# LIDO-HW_100_InputStage_2.net
KiCad netlist of a schematic drawn in Altium Designer
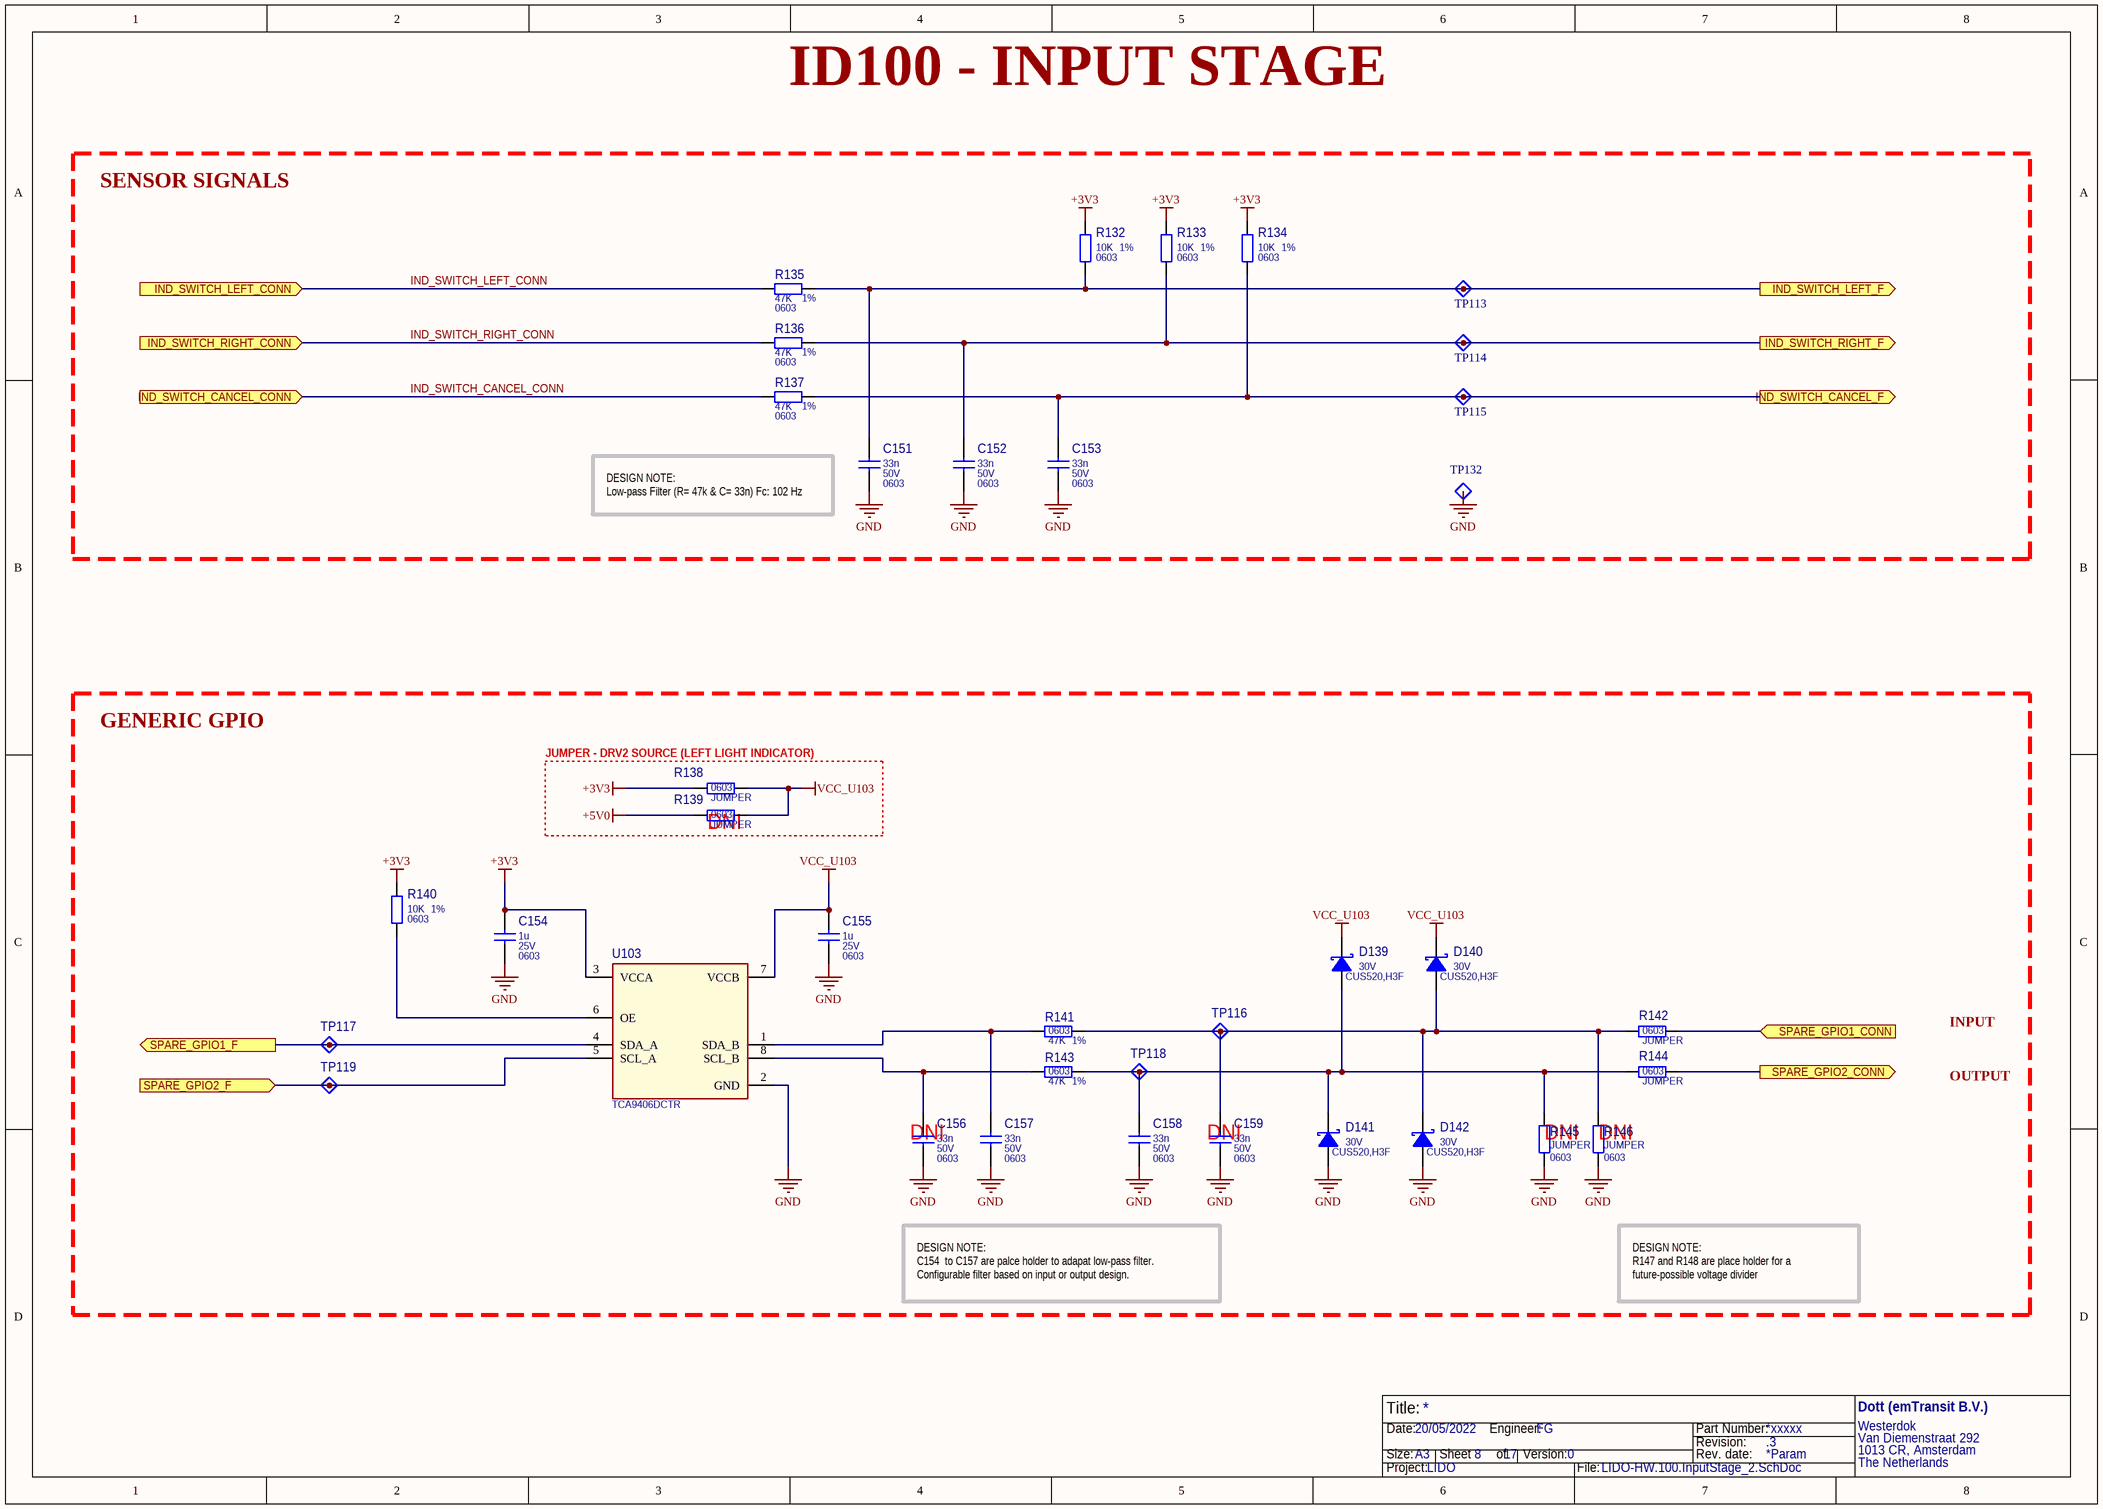
[diagram p0: LIDO-HW.100.InputStage_2.SchDoc]

(export (version "E")
  (design (tool "Eeschema 10.0.6"))
  (components
    (comp (ref "C151")
      (value "33n")
      (footprint "CAP_0603_1608X90-N_MURATA_A")
      (description "CAP CER 0.033UF 50V X7R 0603")
      (fields
        (field (name "MANUFACTURER PART NUMBER") "CGA3E2X7R1H333K080AA")
        (field (name "MANUFACTURER") "TDK Corporation")
        (field (name "PART VALUE 2") "50V")
        (field (name "PART PACKAGE") "0603")
      )
      (libsource (lib "DB_Library") (part "Ceramic"))
    )
    (comp (ref "C152")
      (value "33n")
      (footprint "CAP_0603_1608X90-N_MURATA_A")
      (description "CAP CER 0.033UF 50V X7R 0603")
      (fields
        (field (name "MANUFACTURER PART NUMBER") "CGA3E2X7R1H333K080AA")
        (field (name "MANUFACTURER") "TDK Corporation")
        (field (name "PART VALUE 2") "50V")
        (field (name "PART PACKAGE") "0603")
      )
      (libsource (lib "DB_Library") (part "Ceramic"))
    )
    (comp (ref "C153")
      (value "33n")
      (footprint "CAP_0603_1608X90-N_MURATA_A")
      (description "CAP CER 0.033UF 50V X7R 0603")
      (fields
        (field (name "MANUFACTURER PART NUMBER") "CGA3E2X7R1H333K080AA")
        (field (name "MANUFACTURER") "TDK Corporation")
        (field (name "PART VALUE 2") "50V")
        (field (name "PART PACKAGE") "0603")
      )
      (libsource (lib "DB_Library") (part "Ceramic"))
    )
    (comp (ref "C154")
      (value "1u")
      (footprint "CAP_0603_1608X90-N_MURATA_A")
      (description "CAP CER 1UF 25V X7R 0603")
      (fields
        (field (name "MANUFACTURER PART NUMBER") "CGA3E1X7R1E105M080AE")
        (field (name "MANUFACTURER") "TDK Corporation")
        (field (name "PART VALUE 2") "25V")
        (field (name "PART PACKAGE") "0603")
      )
      (libsource (lib "DB_Library") (part "Ceramic"))
    )
    (comp (ref "C155")
      (value "1u")
      (footprint "CAP_0603_1608X90-N_MURATA_A")
      (description "CAP CER 1UF 25V X7R 0603")
      (fields
        (field (name "MANUFACTURER PART NUMBER") "CGA3E1X7R1E105M080AE")
        (field (name "MANUFACTURER") "TDK Corporation")
        (field (name "PART VALUE 2") "25V")
        (field (name "PART PACKAGE") "0603")
      )
      (libsource (lib "DB_Library") (part "Ceramic"))
    )
    (comp (ref "C156")
      (value "33n")
      (footprint "CAP_0603_1608X90-N_MURATA_A")
      (description "CAP CER 0.033UF 50V X7R 0603")
      (fields
        (field (name "MANUFACTURER PART NUMBER") "CGA3E2X7R1H333K080AA")
        (field (name "MANUFACTURER") "TDK Corporation")
        (field (name "PART VALUE 2") "50V")
        (field (name "PART PACKAGE") "0603")
      )
      (libsource (lib "DB_Library") (part "Ceramic"))
    )
    (comp (ref "C157")
      (value "33n")
      (footprint "CAP_0603_1608X90-N_MURATA_A")
      (description "CAP CER 0.033UF 50V X7R 0603")
      (fields
        (field (name "MANUFACTURER PART NUMBER") "CGA3E2X7R1H333K080AA")
        (field (name "MANUFACTURER") "TDK Corporation")
        (field (name "PART VALUE 2") "50V")
        (field (name "PART PACKAGE") "0603")
      )
      (libsource (lib "DB_Library") (part "Ceramic"))
    )
    (comp (ref "C158")
      (value "33n")
      (footprint "CAP_0603_1608X90-N_MURATA_A")
      (description "CAP CER 0.033UF 50V X7R 0603")
      (fields
        (field (name "MANUFACTURER PART NUMBER") "CGA3E2X7R1H333K080AA")
        (field (name "MANUFACTURER") "TDK Corporation")
        (field (name "PART VALUE 2") "50V")
        (field (name "PART PACKAGE") "0603")
      )
      (libsource (lib "DB_Library") (part "Ceramic"))
    )
    (comp (ref "C159")
      (value "33n")
      (footprint "CAP_0603_1608X90-N_MURATA_A")
      (description "CAP CER 0.033UF 50V X7R 0603")
      (fields
        (field (name "MANUFACTURER PART NUMBER") "CGA3E2X7R1H333K080AA")
        (field (name "MANUFACTURER") "TDK Corporation")
        (field (name "PART VALUE 2") "50V")
        (field (name "PART PACKAGE") "0603")
      )
      (libsource (lib "DB_Library") (part "Ceramic"))
    )
    (comp (ref "D139")
      (value "30V")
      (footprint "NXP_SOD-323_250X125X95L30x32_A")
      (description "DIODE SCHOTTKY 30V 200MA")
      (fields
        (field (name "MANUFACTURER PART NUMBER") "CUS520,H3F")
        (field (name "MANUFACTURER") "Toshiba Semiconductor and Storage")
        (field (name "OBSOLETE PART") "False")
      )
      (libsource (lib "DB_Library") (part "Schottky_A"))
    )
    (comp (ref "D140")
      (value "30V")
      (footprint "NXP_SOD-323_250X125X95L30x32_A")
      (description "DIODE SCHOTTKY 30V 200MA")
      (fields
        (field (name "MANUFACTURER PART NUMBER") "CUS520,H3F")
        (field (name "MANUFACTURER") "Toshiba Semiconductor and Storage")
        (field (name "OBSOLETE PART") "False")
      )
      (libsource (lib "DB_Library") (part "Schottky_A"))
    )
    (comp (ref "D141")
      (value "30V")
      (footprint "NXP_SOD-323_250X125X95L30x32_A")
      (description "DIODE SCHOTTKY 30V 200MA")
      (fields
        (field (name "MANUFACTURER PART NUMBER") "CUS520,H3F")
        (field (name "MANUFACTURER") "Toshiba Semiconductor and Storage")
        (field (name "OBSOLETE PART") "False")
      )
      (libsource (lib "DB_Library") (part "Schottky_A"))
    )
    (comp (ref "D142")
      (value "30V")
      (footprint "NXP_SOD-323_250X125X95L30x32_A")
      (description "DIODE SCHOTTKY 30V 200MA")
      (fields
        (field (name "MANUFACTURER PART NUMBER") "CUS520,H3F")
        (field (name "MANUFACTURER") "Toshiba Semiconductor and Storage")
        (field (name "OBSOLETE PART") "False")
      )
      (libsource (lib "DB_Library") (part "Schottky_A"))
    )
    (comp (ref "R132")
      (value "10K")
      (footprint "RES_0603_1608X60-N_YAGEO_A")
      (description "RES 10K OHM 1% 1/10W 0603")
      (fields
        (field (name "MANUFACTURER PART NUMBER") "RC0603FR-0710KL")
        (field (name "MANUFACTURER") "YAGEO")
        (field (name "PART VALUE 2") "1%")
        (field (name "PART PACKAGE") "0603")
      )
      (libsource (lib "") (part "Resistor_1"))
    )
    (comp (ref "R133")
      (value "10K")
      (footprint "RES_0603_1608X60-N_YAGEO_A")
      (description "RES 10K OHM 1% 1/10W 0603")
      (fields
        (field (name "MANUFACTURER PART NUMBER") "RC0603FR-0710KL")
        (field (name "MANUFACTURER") "YAGEO")
        (field (name "PART VALUE 2") "1%")
        (field (name "PART PACKAGE") "0603")
      )
      (libsource (lib "") (part "Resistor_1"))
    )
    (comp (ref "R134")
      (value "10K")
      (footprint "RES_0603_1608X60-N_YAGEO_A")
      (description "RES 10K OHM 1% 1/10W 0603")
      (fields
        (field (name "MANUFACTURER PART NUMBER") "RC0603FR-0710KL")
        (field (name "MANUFACTURER") "YAGEO")
        (field (name "PART VALUE 2") "1%")
        (field (name "PART PACKAGE") "0603")
      )
      (libsource (lib "") (part "Resistor_1"))
    )
    (comp (ref "R135")
      (value "47K")
      (footprint "RES_0603_1608X60-N_YAGEO_A")
      (description "RES SMD 47K OHM 1% 1/10W 0603")
      (fields
        (field (name "MANUFACTURER PART NUMBER") "ERJ-3EKF4702V")
        (field (name "MANUFACTURER") "Panasonic Electronic Components")
        (field (name "PART VALUE 2") "1%")
        (field (name "PART PACKAGE") "0603")
      )
      (libsource (lib "DB_Library") (part "Resistor"))
    )
    (comp (ref "R136")
      (value "47K")
      (footprint "RES_0603_1608X60-N_YAGEO_A")
      (description "RES SMD 47K OHM 1% 1/10W 0603")
      (fields
        (field (name "MANUFACTURER PART NUMBER") "ERJ-3EKF4702V")
        (field (name "MANUFACTURER") "Panasonic Electronic Components")
        (field (name "PART VALUE 2") "1%")
        (field (name "PART PACKAGE") "0603")
      )
      (libsource (lib "DB_Library") (part "Resistor"))
    )
    (comp (ref "R137")
      (value "47K")
      (footprint "RES_0603_1608X60-N_YAGEO_A")
      (description "RES SMD 47K OHM 1% 1/10W 0603")
      (fields
        (field (name "MANUFACTURER PART NUMBER") "ERJ-3EKF4702V")
        (field (name "MANUFACTURER") "Panasonic Electronic Components")
        (field (name "PART VALUE 2") "1%")
        (field (name "PART PACKAGE") "0603")
      )
      (libsource (lib "DB_Library") (part "Resistor"))
    )
    (comp (ref "R138")
      (value "JUMPER")
      (footprint "RES_0603_1608X60-N_YAGEO_A")
      (description "RES 0 OHM JUMPER 1/10W 0603")
      (fields
        (field (name "MANUFACTURER PART NUMBER") "RC0603JR-070RL")
        (field (name "MANUFACTURER") "YAGEO")
        (field (name "PART PACKAGE") "0603")
      )
      (libsource (lib "DB_Library") (part "Resistor"))
    )
    (comp (ref "R139")
      (value "JUMPER")
      (footprint "RES_0603_1608X60-N_YAGEO_A")
      (description "RES 0 OHM JUMPER 1/10W 0603")
      (fields
        (field (name "MANUFACTURER PART NUMBER") "RC0603JR-070RL")
        (field (name "MANUFACTURER") "YAGEO")
        (field (name "PART PACKAGE") "0603")
      )
      (libsource (lib "DB_Library") (part "Resistor"))
    )
    (comp (ref "R140")
      (value "10K")
      (footprint "RES_0603_1608X60-N_YAGEO_A")
      (description "RES 10K OHM 1% 1/10W 0603")
      (fields
        (field (name "MANUFACTURER PART NUMBER") "RC0603FR-0710KL")
        (field (name "MANUFACTURER") "YAGEO")
        (field (name "PART VALUE 2") "1%")
        (field (name "PART PACKAGE") "0603")
      )
      (libsource (lib "") (part "Resistor_1"))
    )
    (comp (ref "R141")
      (value "47K")
      (footprint "RES_0603_1608X60-N_YAGEO_A")
      (description "RES SMD 47K OHM 1% 1/10W 0603")
      (fields
        (field (name "MANUFACTURER PART NUMBER") "ERJ-3EKF4702V")
        (field (name "MANUFACTURER") "Panasonic Electronic Components")
        (field (name "PART VALUE 2") "1%")
        (field (name "PART PACKAGE") "0603")
      )
      (libsource (lib "DB_Library") (part "Resistor"))
    )
    (comp (ref "R142")
      (value "JUMPER")
      (footprint "RES_0603_1608X60-N_YAGEO_A")
      (description "RES 0 OHM JUMPER 1/10W 0603")
      (fields
        (field (name "MANUFACTURER PART NUMBER") "RC0603JR-070RL")
        (field (name "MANUFACTURER") "YAGEO")
        (field (name "PART PACKAGE") "0603")
      )
      (libsource (lib "DB_Library") (part "Resistor"))
    )
    (comp (ref "R143")
      (value "47K")
      (footprint "RES_0603_1608X60-N_YAGEO_A")
      (description "RES SMD 47K OHM 1% 1/10W 0603")
      (fields
        (field (name "MANUFACTURER PART NUMBER") "ERJ-3EKF4702V")
        (field (name "MANUFACTURER") "Panasonic Electronic Components")
        (field (name "PART VALUE 2") "1%")
        (field (name "PART PACKAGE") "0603")
      )
      (libsource (lib "DB_Library") (part "Resistor"))
    )
    (comp (ref "R144")
      (value "JUMPER")
      (footprint "RES_0603_1608X60-N_YAGEO_A")
      (description "RES 0 OHM JUMPER 1/10W 0603")
      (fields
        (field (name "MANUFACTURER PART NUMBER") "RC0603JR-070RL")
        (field (name "MANUFACTURER") "YAGEO")
        (field (name "PART PACKAGE") "0603")
      )
      (libsource (lib "DB_Library") (part "Resistor"))
    )
    (comp (ref "R145")
      (value "JUMPER")
      (footprint "RES_0603_1608X60-N_YAGEO_A")
      (description "RES 0 OHM JUMPER 1/10W 0603")
      (fields
        (field (name "MANUFACTURER PART NUMBER") "RC0603JR-070RL")
        (field (name "MANUFACTURER") "YAGEO")
        (field (name "PART PACKAGE") "0603")
      )
      (libsource (lib "") (part "Resistor_1"))
    )
    (comp (ref "R146")
      (value "JUMPER")
      (footprint "RES_0603_1608X60-N_YAGEO_A")
      (description "RES 0 OHM JUMPER 1/10W 0603")
      (fields
        (field (name "MANUFACTURER PART NUMBER") "RC0603JR-070RL")
        (field (name "MANUFACTURER") "YAGEO")
        (field (name "PART PACKAGE") "0603")
      )
      (libsource (lib "") (part "Resistor_1"))
    )
    (comp (ref "TP113")
      (value "TestPoint_A")
      (footprint "TESTPOINT_1D_A")
      (description "Pad Diamater 1mm")
      (fields (field (name "PART") "Test Point 1D A") (field (name "OBSOLETE PART") "False"))
      (libsource (lib "DB_Library") (part "TestPoint_A"))
    )
    (comp (ref "TP114")
      (value "TestPoint_A")
      (footprint "TESTPOINT_1D_A")
      (description "Pad Diamater 1mm")
      (fields (field (name "PART") "Test Point 1D A") (field (name "OBSOLETE PART") "False"))
      (libsource (lib "DB_Library") (part "TestPoint_A"))
    )
    (comp (ref "TP115")
      (value "TestPoint_A")
      (footprint "TESTPOINT_1D_A")
      (description "Pad Diamater 1mm")
      (fields (field (name "PART") "Test Point 1D A") (field (name "OBSOLETE PART") "False"))
      (libsource (lib "DB_Library") (part "TestPoint_A"))
    )
    (comp (ref "TP116")
      (value "TestPoint_A")
      (footprint "TESTPOINT_1D_A")
      (description "Pad Diamater 1mm")
      (fields (field (name "PART") "Test Point 1D A") (field (name "OBSOLETE PART") "False"))
      (libsource (lib "DB_Library") (part "TestPoint_A"))
    )
    (comp (ref "TP117")
      (value "TestPoint_A")
      (footprint "TESTPOINT_1D_A")
      (description "Pad Diamater 1mm")
      (fields (field (name "PART") "Test Point 1D A") (field (name "OBSOLETE PART") "False"))
      (libsource (lib "DB_Library") (part "TestPoint_A"))
    )
    (comp (ref "TP118")
      (value "TestPoint_A")
      (footprint "TESTPOINT_1D_A")
      (description "Pad Diamater 1mm")
      (fields (field (name "PART") "Test Point 1D A") (field (name "OBSOLETE PART") "False"))
      (libsource (lib "DB_Library") (part "TestPoint_A"))
    )
    (comp (ref "TP119")
      (value "TestPoint_A")
      (footprint "TESTPOINT_1D_A")
      (description "Pad Diamater 1mm")
      (fields (field (name "PART") "Test Point 1D A") (field (name "OBSOLETE PART") "False"))
      (libsource (lib "DB_Library") (part "TestPoint_A"))
    )
    (comp (ref "TP132")
      (value "TestPoint_A")
      (footprint "TESTPOINT_1D_A")
      (description "Pad Diamater 1mm")
      (fields (field (name "PART") "Test Point 1D A") (field (name "OBSOLETE PART") "False"))
      (libsource (lib "DB_Library") (part "TestPoint_A"))
    )
    (comp (ref "U103")
      (value "TCA9406DCTR")
      (footprint "SSOP8P65_295X400X130L40X25-N_TI_A")
      (description "Voltage Level Translator Bidirectional 1 Circuit 2 Channel 24Mbps SM8")
      (fields (field (name "MANUFACTURER") "Texas Instruments") (field (name "OBSOLETE PART") "False"))
      (libsource (lib "DB_Library") (part "TCA9406_A"))
    )
  )
  (nets
    (net (code "1") (name "+3V3") (class "Default")
      (node (ref "C154") (pin "1") (pinfunction "1_1") (pintype "passive"))
      (node (ref "R132") (pin "2") (pinfunction "2_2") (pintype "passive"))
      (node (ref "R133") (pin "2") (pinfunction "2_2") (pintype "passive"))
      (node (ref "R134") (pin "2") (pinfunction "2_2") (pintype "passive"))
      (node (ref "R138") (pin "1") (pinfunction "1_1") (pintype "passive"))
      (node (ref "R140") (pin "2") (pinfunction "2_2") (pintype "passive"))
      (node (ref "U103") (pin "3") (pinfunction "VCCA_3") (pintype "power_in"))
    )
    (net (code "2") (name "+5V0") (class "Default")
      (node (ref "R139") (pin "1") (pinfunction "1_1") (pintype "passive"))
    )
    (net (code "3") (name "/IND_SWITCH_CANCEL_CONN") (class "Default")
      (node (ref "R137") (pin "1") (pinfunction "1_1") (pintype "passive"))
    )
    (net (code "4") (name "/IND_SWITCH_CANCEL_F") (class "Default")
      (node (ref "C153") (pin "1") (pinfunction "1_1") (pintype "passive"))
      (node (ref "R134") (pin "1") (pinfunction "1_1") (pintype "passive"))
      (node (ref "R137") (pin "2") (pinfunction "2_2") (pintype "passive"))
      (node (ref "TP115") (pin "1") (pinfunction "TP_1") (pintype "passive"))
    )
    (net (code "5") (name "/IND_SWITCH_LEFT_CONN") (class "Default")
      (node (ref "R135") (pin "1") (pinfunction "1_1") (pintype "passive"))
    )
    (net (code "6") (name "/IND_SWITCH_LEFT_F") (class "Default")
      (node (ref "C151") (pin "1") (pinfunction "1_1") (pintype "passive"))
      (node (ref "R132") (pin "1") (pinfunction "1_1") (pintype "passive"))
      (node (ref "R135") (pin "2") (pinfunction "2_2") (pintype "passive"))
      (node (ref "TP113") (pin "1") (pinfunction "TP_1") (pintype "passive"))
    )
    (net (code "7") (name "/IND_SWITCH_RIGHT_CONN") (class "Default")
      (node (ref "R136") (pin "1") (pinfunction "1_1") (pintype "passive"))
    )
    (net (code "8") (name "/IND_SWITCH_RIGHT_F") (class "Default")
      (node (ref "C152") (pin "1") (pinfunction "1_1") (pintype "passive"))
      (node (ref "R133") (pin "1") (pinfunction "1_1") (pintype "passive"))
      (node (ref "R136") (pin "2") (pinfunction "2_2") (pintype "passive"))
      (node (ref "TP114") (pin "1") (pinfunction "TP_1") (pintype "passive"))
    )
    (net (code "9") (name "/SPARE_GPIO1_CONN") (class "Default")
      (node (ref "R142") (pin "2") (pinfunction "2_2") (pintype "passive"))
    )
    (net (code "10") (name "/SPARE_GPIO1_F") (class "Default")
      (node (ref "TP117") (pin "1") (pinfunction "TP_1") (pintype "passive"))
      (node (ref "U103") (pin "4") (pinfunction "SDA_A_4") (pintype "passive"))
    )
    (net (code "11") (name "/SPARE_GPIO2_CONN") (class "Default")
      (node (ref "R144") (pin "2") (pinfunction "2_2") (pintype "passive"))
    )
    (net (code "12") (name "/SPARE_GPIO2_F") (class "Default")
      (node (ref "TP119") (pin "1") (pinfunction "TP_1") (pintype "passive"))
      (node (ref "U103") (pin "5") (pinfunction "SCL_A_5") (pintype "passive"))
    )
    (net (code "13") (name "GND") (class "Default")
      (node (ref "C151") (pin "2") (pinfunction "2_2") (pintype "passive"))
      (node (ref "C152") (pin "2") (pinfunction "2_2") (pintype "passive"))
      (node (ref "C153") (pin "2") (pinfunction "2_2") (pintype "passive"))
      (node (ref "C154") (pin "2") (pinfunction "2_2") (pintype "passive"))
      (node (ref "C155") (pin "2") (pinfunction "2_2") (pintype "passive"))
      (node (ref "C156") (pin "2") (pinfunction "2_2") (pintype "passive"))
      (node (ref "C157") (pin "2") (pinfunction "2_2") (pintype "passive"))
      (node (ref "C158") (pin "2") (pinfunction "2_2") (pintype "passive"))
      (node (ref "C159") (pin "2") (pinfunction "2_2") (pintype "passive"))
      (node (ref "D141") (pin "A") (pinfunction "A_A") (pintype "passive"))
      (node (ref "D142") (pin "A") (pinfunction "A_A") (pintype "passive"))
      (node (ref "R145") (pin "1") (pinfunction "1_1") (pintype "passive"))
      (node (ref "R146") (pin "1") (pinfunction "1_1") (pintype "passive"))
      (node (ref "TP132") (pin "1") (pinfunction "TP_1") (pintype "passive"))
      (node (ref "U103") (pin "2") (pinfunction "GND_2") (pintype "power_in"))
    )
    (net (code "14") (name "Net-(TP116-TP)") (class "Default")
      (node (ref "C159") (pin "1") (pinfunction "1_1") (pintype "passive"))
      (node (ref "D140") (pin "A") (pinfunction "A_A") (pintype "passive"))
      (node (ref "D142") (pin "C") (pinfunction "C_C") (pintype "passive"))
      (node (ref "R141") (pin "2") (pinfunction "2_2") (pintype "passive"))
      (node (ref "R142") (pin "1") (pinfunction "1_1") (pintype "passive"))
      (node (ref "R146") (pin "2") (pinfunction "2_2") (pintype "passive"))
      (node (ref "TP116") (pin "1") (pinfunction "TP_1") (pintype "passive"))
    )
    (net (code "15") (name "Net-(TP118-TP)") (class "Default")
      (node (ref "C158") (pin "1") (pinfunction "1_1") (pintype "passive"))
      (node (ref "D139") (pin "A") (pinfunction "A_A") (pintype "passive"))
      (node (ref "D141") (pin "C") (pinfunction "C_C") (pintype "passive"))
      (node (ref "R143") (pin "2") (pinfunction "2_2") (pintype "passive"))
      (node (ref "R144") (pin "1") (pinfunction "1_1") (pintype "passive"))
      (node (ref "R145") (pin "2") (pinfunction "2_2") (pintype "passive"))
      (node (ref "TP118") (pin "1") (pinfunction "TP_1") (pintype "passive"))
    )
    (net (code "16") (name "Net-(U103-OE)") (class "Default")
      (node (ref "R140") (pin "1") (pinfunction "1_1") (pintype "passive"))
      (node (ref "U103") (pin "6") (pinfunction "OE_6") (pintype "passive"))
    )
    (net (code "17") (name "Net-(U103-SCL_B)") (class "Default")
      (node (ref "C156") (pin "1") (pinfunction "1_1") (pintype "passive"))
      (node (ref "R143") (pin "1") (pinfunction "1_1") (pintype "passive"))
      (node (ref "U103") (pin "8") (pinfunction "SCL_B_8") (pintype "passive"))
    )
    (net (code "18") (name "Net-(U103-SDA_B)") (class "Default")
      (node (ref "C157") (pin "1") (pinfunction "1_1") (pintype "passive"))
      (node (ref "R141") (pin "1") (pinfunction "1_1") (pintype "passive"))
      (node (ref "U103") (pin "1") (pinfunction "SDA_B_1") (pintype "passive"))
    )
    (net (code "19") (name "VCC_U103") (class "Default")
      (node (ref "C155") (pin "1") (pinfunction "1_1") (pintype "passive"))
      (node (ref "D139") (pin "C") (pinfunction "C_C") (pintype "passive"))
      (node (ref "D140") (pin "C") (pinfunction "C_C") (pintype "passive"))
      (node (ref "R138") (pin "2") (pinfunction "2_2") (pintype "passive"))
      (node (ref "R139") (pin "2") (pinfunction "2_2") (pintype "passive"))
      (node (ref "U103") (pin "7") (pinfunction "VCCB_7") (pintype "power_in"))
    )
  )
)
